# GLEE_Testing_01_Advait.net
KiCad netlist of a schematic drawn in EAGLE
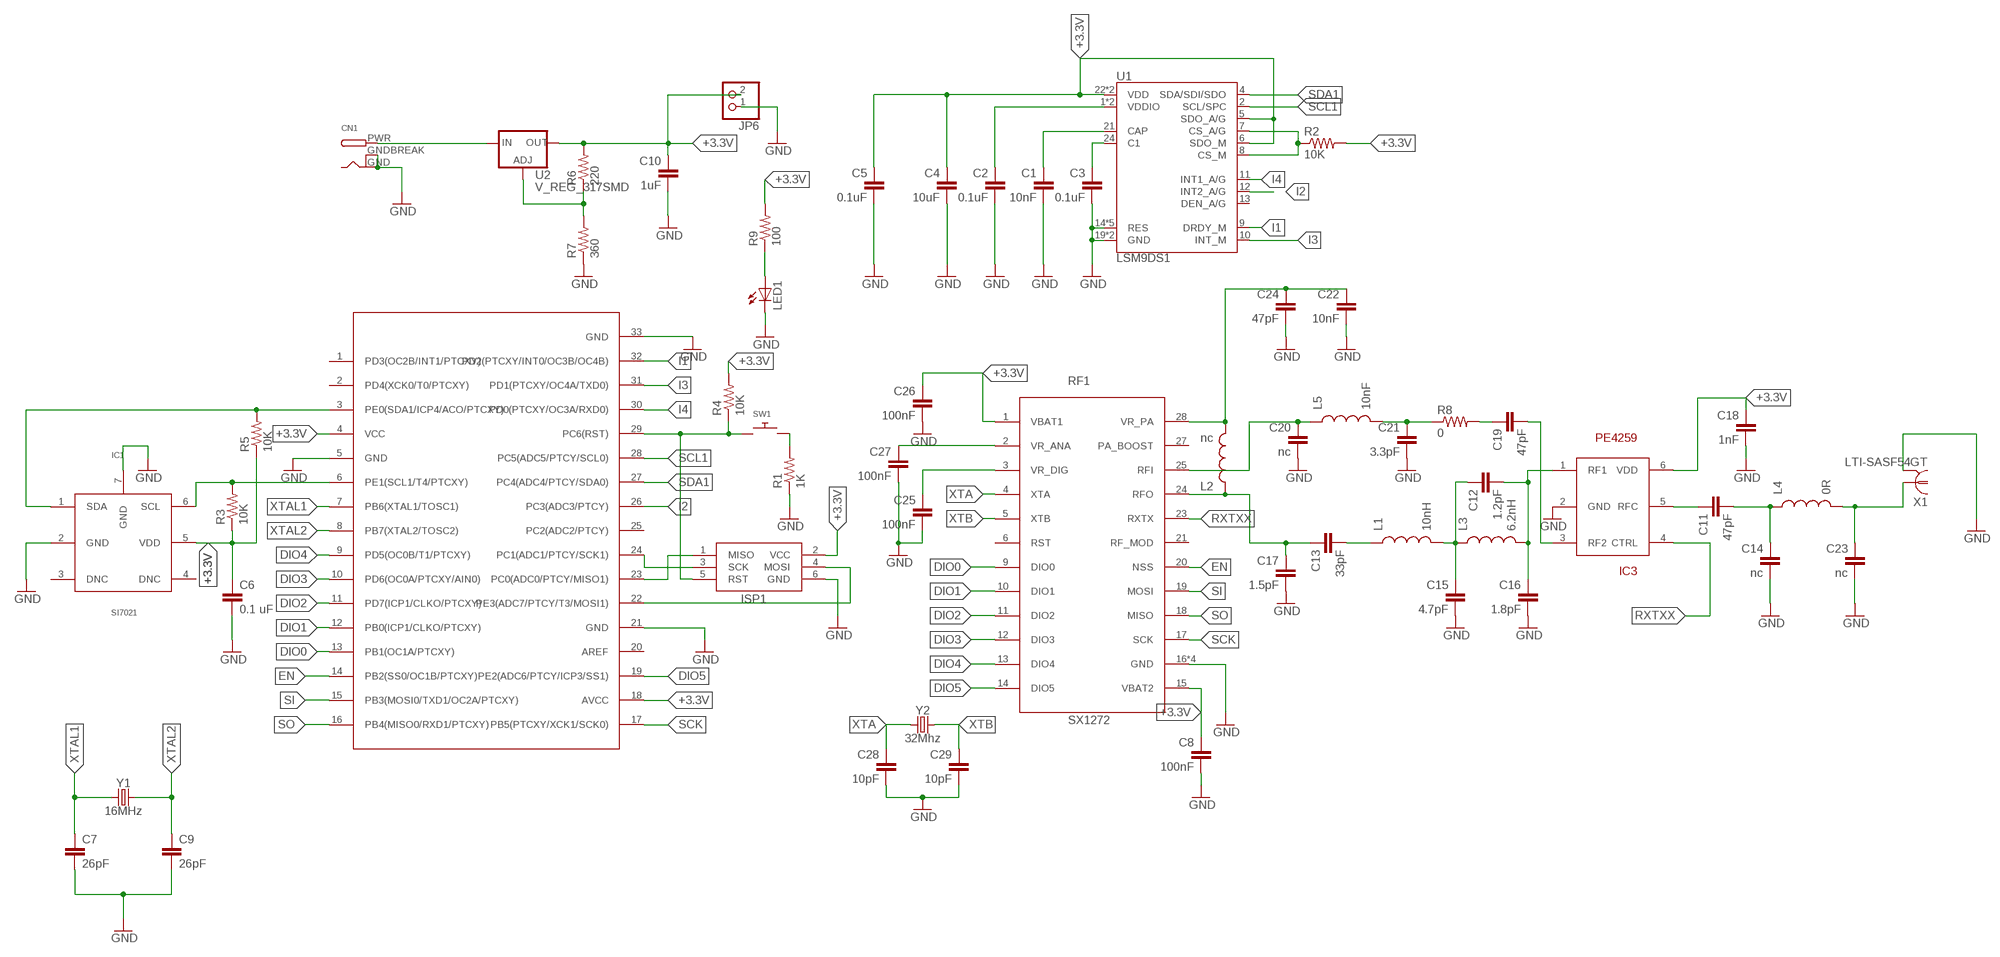
[diagram p0: schematic, sheet 1]

(export (version "E")
  (design (tool "Eeschema 10.0.6"))
  (components
    (comp (ref "C1")
      (value "10nF")
      (footprint "eagle-import:0402-CAP")
      (libsource (lib "eagle-import") (part "CAP0402-CAP"))
    )
    (comp (ref "C2")
      (value "0.1uF")
      (footprint "eagle-import:0402-CAP")
      (libsource (lib "eagle-import") (part "CAP0402-CAP"))
    )
    (comp (ref "C3")
      (value "0.1uF")
      (footprint "eagle-import:0402-CAP")
      (libsource (lib "eagle-import") (part "CAP0402-CAP"))
    )
    (comp (ref "C4")
      (value "10uF")
      (footprint "eagle-import:0402-CAP")
      (libsource (lib "eagle-import") (part "CAP0402-CAP"))
    )
    (comp (ref "C5")
      (value "0.1uF")
      (footprint "eagle-import:0402-CAP")
      (libsource (lib "eagle-import") (part "CAP0402-CAP"))
    )
    (comp (ref "C6")
      (value "0.1 uF")
      (footprint "eagle-import:0402-CAP")
      (libsource (lib "eagle-import") (part "CAP0402-CAP"))
    )
    (comp (ref "C7")
      (value "26pF")
      (footprint "eagle-import:0402-CAP")
      (libsource (lib "eagle-import") (part "CAP0402-CAP"))
    )
    (comp (ref "C8")
      (value "100nF")
      (footprint "eagle-import:0402-CAP")
      (libsource (lib "eagle-import") (part "CAP0402-CAP"))
    )
    (comp (ref "C9")
      (value "26pF")
      (footprint "eagle-import:0402-CAP")
      (libsource (lib "eagle-import") (part "CAP0402-CAP"))
    )
    (comp (ref "C10")
      (value "1uF")
      (footprint "eagle-import:0402-CAP")
      (libsource (lib "eagle-import") (part "CAP0402-CAP"))
    )
    (comp (ref "C11")
      (value "47pF")
      (footprint "eagle-import:0402-CAP")
      (libsource (lib "eagle-import") (part "CAP0402-CAP"))
    )
    (comp (ref "C12")
      (value "1.2pF")
      (footprint "eagle-import:0402-CAP")
      (libsource (lib "eagle-import") (part "CAP0402-CAP"))
    )
    (comp (ref "C13")
      (value "33pF")
      (footprint "eagle-import:0402-CAP")
      (libsource (lib "eagle-import") (part "CAP0402-CAP"))
    )
    (comp (ref "C14")
      (value "nc")
      (footprint "eagle-import:0402-CAP")
      (libsource (lib "eagle-import") (part "CAP0402-CAP"))
    )
    (comp (ref "C15")
      (value "4.7pF")
      (footprint "eagle-import:0402-CAP")
      (libsource (lib "eagle-import") (part "CAP0402-CAP"))
    )
    (comp (ref "C16")
      (value "1.8pF")
      (footprint "eagle-import:0402-CAP")
      (libsource (lib "eagle-import") (part "CAP0402-CAP"))
    )
    (comp (ref "C17")
      (value "1.5pF")
      (footprint "eagle-import:0402-CAP")
      (libsource (lib "eagle-import") (part "CAP0402-CAP"))
    )
    (comp (ref "C18")
      (value "1nF")
      (footprint "eagle-import:0402-CAP")
      (libsource (lib "eagle-import") (part "CAP0402-CAP"))
    )
    (comp (ref "C19")
      (value "47pF")
      (footprint "eagle-import:0402-CAP")
      (libsource (lib "eagle-import") (part "CAP0402-CAP"))
    )
    (comp (ref "C20")
      (value "nc")
      (footprint "eagle-import:0402-CAP")
      (libsource (lib "eagle-import") (part "CAP0402-CAP"))
    )
    (comp (ref "C21")
      (value "3.3pF")
      (footprint "eagle-import:0402-CAP")
      (libsource (lib "eagle-import") (part "CAP0402-CAP"))
    )
    (comp (ref "C22")
      (value "10nF")
      (footprint "eagle-import:0402-CAP")
      (libsource (lib "eagle-import") (part "CAP0402-CAP"))
    )
    (comp (ref "C23")
      (value "nc")
      (footprint "eagle-import:0402-CAP")
      (libsource (lib "eagle-import") (part "CAP0402-CAP"))
    )
    (comp (ref "C24")
      (value "47pF")
      (footprint "eagle-import:0402-CAP")
      (libsource (lib "eagle-import") (part "CAP0402-CAP"))
    )
    (comp (ref "C25")
      (value "100nF")
      (footprint "eagle-import:0402-CAP")
      (libsource (lib "eagle-import") (part "CAP0402-CAP"))
    )
    (comp (ref "C26")
      (value "100nF")
      (footprint "eagle-import:0402-CAP")
      (libsource (lib "eagle-import") (part "CAP0402-CAP"))
    )
    (comp (ref "C27")
      (value "100nF")
      (footprint "eagle-import:0402-CAP")
      (libsource (lib "eagle-import") (part "CAP0402-CAP"))
    )
    (comp (ref "C28")
      (value "10pF")
      (footprint "eagle-import:0402-CAP")
      (libsource (lib "eagle-import") (part "CAP0402-CAP"))
    )
    (comp (ref "C29")
      (value "10pF")
      (footprint "eagle-import:0402-CAP")
      (libsource (lib "eagle-import") (part "CAP0402-CAP"))
    )
    (comp (ref "CN1")
      (value "DCBARRELPTH")
      (footprint "eagle-import:DCJACK_2MM_PTH")
      (libsource (lib "eagle-import") (part "DCBARRELPTH"))
    )
    (comp (ref "IC1")
      (value "SI7021")
      (footprint "eagle-import:SI7021")
      (libsource (lib "eagle-import") (part "SI7021"))
    )
    (comp (ref "IC2")
      (value "ATMEGA328-PB")
      (footprint "eagle-import:ATMEGA328-PB")
      (libsource (lib "eagle-import") (part "ATMEGA328-PB"))
    )
    (comp (ref "IC3")
      (value "PE4259")
      (footprint "eagle-import:PE4259")
      (libsource (lib "eagle-import") (part "PE4259"))
    )
    (comp (ref "ISP1")
      (value "AVRISP-6")
      (footprint "eagle-import:AVRISP")
      (libsource (lib "eagle-import") (part "AVRISP-6"))
    )
    (comp (ref "JP6")
      (value "PINHD-1X2")
      (footprint "eagle-import:1X02")
      (libsource (lib "eagle-import") (part "PINHD-1X2"))
    )
    (comp (ref "L1")
      (value "10nH")
      (footprint "eagle-import:C0402")
      (libsource (lib "eagle-import") (part "INDUCTOR0402"))
    )
    (comp (ref "L2")
      (value "nc")
      (footprint "eagle-import:C0402")
      (libsource (lib "eagle-import") (part "INDUCTOR0402"))
    )
    (comp (ref "L3")
      (value "6.2nH")
      (footprint "eagle-import:C0402")
      (libsource (lib "eagle-import") (part "INDUCTOR0402"))
    )
    (comp (ref "L4")
      (value "0R")
      (footprint "eagle-import:C0402")
      (libsource (lib "eagle-import") (part "INDUCTOR0402"))
    )
    (comp (ref "L5")
      (value "10nF")
      (footprint "eagle-import:C0402")
      (libsource (lib "eagle-import") (part "INDUCTOR0402"))
    )
    (comp (ref "LED1")
      (value "LEDCHIPLED_0805")
      (footprint "eagle-import:CHIPLED_0805")
      (libsource (lib "eagle-import") (part "LEDCHIPLED_0805"))
    )
    (comp (ref "R1")
      (value "1K")
      (footprint "eagle-import:0402-RES")
      (libsource (lib "eagle-import") (part "RESISTOR0402-RES"))
    )
    (comp (ref "R2")
      (value "10K")
      (footprint "eagle-import:0402-RES")
      (libsource (lib "eagle-import") (part "RESISTOR0402-RES"))
    )
    (comp (ref "R3")
      (value "10K")
      (footprint "eagle-import:0402-RES")
      (libsource (lib "eagle-import") (part "RESISTOR0402-RES"))
    )
    (comp (ref "R4")
      (value "10K")
      (footprint "eagle-import:0402-RES")
      (libsource (lib "eagle-import") (part "RESISTOR0402-RES"))
    )
    (comp (ref "R5")
      (value "10K")
      (footprint "eagle-import:0402-RES")
      (libsource (lib "eagle-import") (part "RESISTOR0402-RES"))
    )
    (comp (ref "R6")
      (value "220")
      (footprint "eagle-import:0402-RES")
      (libsource (lib "eagle-import") (part "RESISTOR0402-RES"))
    )
    (comp (ref "R7")
      (value "360")
      (footprint "eagle-import:0402-RES")
      (libsource (lib "eagle-import") (part "RESISTOR0402-RES"))
    )
    (comp (ref "R8")
      (value "0")
      (footprint "eagle-import:0402-RES")
      (libsource (lib "eagle-import") (part "RESISTOR0402-RES"))
    )
    (comp (ref "R9")
      (value "100")
      (footprint "eagle-import:0402-RES")
      (libsource (lib "eagle-import") (part "RESISTOR0402-RES"))
    )
    (comp (ref "RF1")
      (value "SX1272")
      (footprint "eagle-import:SX1272")
      (libsource (lib "eagle-import") (part "SX1272"))
    )
    (comp (ref "SW1")
      (value "SWITCH_PUSHBUTTONSOFTTOUCHSMD_SJ")
      (footprint "eagle-import:PUSHBUTTON_SMD_SJ")
      (libsource (lib "eagle-import") (part "SWITCH_PUSHBUTTONSOFTTOUCHSMD_SJ"))
    )
    (comp (ref "U1")
      (value "LSM9DS1")
      (footprint "eagle-import:LGA24-8X4")
      (libsource (lib "eagle-import") (part "LSM9DS1"))
    )
    (comp (ref "U2")
      (value "V_REG_317SMD")
      (footprint "eagle-import:SOT223")
      (libsource (lib "eagle-import") (part "V_REG_317SMD"))
    )
    (comp (ref "X1")
      (value "LTI-SASF54GT")
      (footprint "eagle-import:LTI-SASF54GT")
      (libsource (lib "eagle-import") (part "LTI-SASF54GT"))
    )
    (comp (ref "Y1")
      (value "16MHz")
      (footprint "eagle-import:CRYSTAL-SMD-2.0X1.6MM")
      (libsource (lib "eagle-import") (part "CRYSTAL-16MHZSMD-2X1.6"))
    )
    (comp (ref "Y2")
      (value "32Mhz")
      (footprint "eagle-import:CRYSTAL-SMD-2.0X1.6MM")
      (libsource (lib "eagle-import") (part "CRYSTAL-16MHZSMD-2X1.6"))
    )
  )
  (nets
    (net (code "1") (name "+3.3V") (class "Default")
      (node (ref "C10") (pin "1") (pinfunction "1_1") (pintype "passive"))
      (node (ref "C18") (pin "1") (pinfunction "1_1") (pintype "passive"))
      (node (ref "C26") (pin "1") (pinfunction "1_1") (pintype "passive"))
      (node (ref "C4") (pin "1") (pinfunction "1_1") (pintype "passive"))
      (node (ref "C5") (pin "1") (pinfunction "1_1") (pintype "passive"))
      (node (ref "C6") (pin "1") (pinfunction "1_1") (pintype "passive"))
      (node (ref "C8") (pin "1") (pinfunction "1_1") (pintype "passive"))
      (node (ref "IC1") (pin "5") (pinfunction "VDD_5") (pintype "bidirectional"))
      (node (ref "IC2") (pin "18") (pinfunction "AVCC_18") (pintype "bidirectional"))
      (node (ref "IC2") (pin "4") (pinfunction "VCC_4") (pintype "bidirectional"))
      (node (ref "IC3") (pin "6") (pinfunction "VDD_6") (pintype "bidirectional"))
      (node (ref "ISP1") (pin "2") (pinfunction "VCC_2") (pintype "power_in"))
      (node (ref "JP6") (pin "2") (pinfunction "2_2") (pintype "passive"))
      (node (ref "R2") (pin "2") (pinfunction "2_2") (pintype "passive"))
      (node (ref "R3") (pin "1") (pinfunction "1_1") (pintype "passive"))
      (node (ref "R4") (pin "2") (pinfunction "2_2") (pintype "passive"))
      (node (ref "R5") (pin "1") (pinfunction "1_1") (pintype "passive"))
      (node (ref "R6") (pin "2") (pinfunction "2_2") (pintype "passive"))
      (node (ref "R9") (pin "2") (pinfunction "2_2") (pintype "passive"))
      (node (ref "RF1") (pin "1") (pinfunction "VBAT1_1") (pintype "bidirectional"))
      (node (ref "RF1") (pin "15") (pinfunction "VBAT2_15") (pintype "bidirectional"))
      (node (ref "U1") (pin "22") (pinfunction "VDD_22") (pintype "bidirectional"))
      (node (ref "U1") (pin "23") (pinfunction "VDD_23") (pintype "bidirectional"))
      (node (ref "U1") (pin "5") (pinfunction "SDO_A/G_5") (pintype "bidirectional"))
      (node (ref "U1") (pin "6") (pinfunction "SDO_M_6") (pintype "bidirectional"))
      (node (ref "U2") (pin "2") (pinfunction "OUT_2") (pintype "output"))
    )
    (net (code "2") (name "DIO0") (class "Default")
      (node (ref "IC2") (pin "13") (pinfunction "PB1(OC1A/PTCXY)_13") (pintype "bidirectional"))
      (node (ref "RF1") (pin "9") (pinfunction "DIO0_9") (pintype "bidirectional"))
    )
    (net (code "3") (name "DIO1") (class "Default")
      (node (ref "IC2") (pin "12") (pinfunction "PB0(ICP1/CLKO/PTCXY)_12") (pintype "bidirectional"))
      (node (ref "RF1") (pin "10") (pinfunction "DIO1_10") (pintype "bidirectional"))
    )
    (net (code "4") (name "DIO2") (class "Default")
      (node (ref "IC2") (pin "11") (pinfunction "PD7(ICP1/CLKO/PTCXY)_11") (pintype "bidirectional"))
      (node (ref "RF1") (pin "11") (pinfunction "DIO2_11") (pintype "bidirectional"))
    )
    (net (code "5") (name "DIO3") (class "Default")
      (node (ref "IC2") (pin "10") (pinfunction "PD6(OC0A/PTCXY/AIN0)_10") (pintype "bidirectional"))
      (node (ref "RF1") (pin "12") (pinfunction "DIO3_12") (pintype "bidirectional"))
    )
    (net (code "6") (name "DIO4") (class "Default")
      (node (ref "IC2") (pin "9") (pinfunction "PD5(OC0B/T1/PTCXY)_9") (pintype "bidirectional"))
      (node (ref "RF1") (pin "13") (pinfunction "DIO4_13") (pintype "bidirectional"))
    )
    (net (code "7") (name "DIO5") (class "Default")
      (node (ref "IC2") (pin "19") (pinfunction "PE2(ADC6/PTCY/ICP3/SS1)_19") (pintype "bidirectional"))
      (node (ref "RF1") (pin "14") (pinfunction "DIO5_14") (pintype "bidirectional"))
    )
    (net (code "8") (name "EN") (class "Default")
      (node (ref "IC2") (pin "14") (pinfunction "PB2(SS0/OC1B/PTCXY)_14") (pintype "bidirectional"))
      (node (ref "RF1") (pin "20") (pinfunction "NSS_20") (pintype "bidirectional"))
    )
    (net (code "9") (name "GND") (class "Default")
      (node (ref "C1") (pin "2") (pinfunction "2_2") (pintype "passive"))
      (node (ref "C10") (pin "2") (pinfunction "2_2") (pintype "passive"))
      (node (ref "C14") (pin "2") (pinfunction "2_2") (pintype "passive"))
      (node (ref "C15") (pin "2") (pinfunction "2_2") (pintype "passive"))
      (node (ref "C16") (pin "2") (pinfunction "2_2") (pintype "passive"))
      (node (ref "C17") (pin "2") (pinfunction "2_2") (pintype "passive"))
      (node (ref "C18") (pin "2") (pinfunction "2_2") (pintype "passive"))
      (node (ref "C2") (pin "2") (pinfunction "2_2") (pintype "passive"))
      (node (ref "C20") (pin "2") (pinfunction "2_2") (pintype "passive"))
      (node (ref "C21") (pin "2") (pinfunction "2_2") (pintype "passive"))
      (node (ref "C22") (pin "2") (pinfunction "2_2") (pintype "passive"))
      (node (ref "C23") (pin "2") (pinfunction "2_2") (pintype "passive"))
      (node (ref "C24") (pin "2") (pinfunction "2_2") (pintype "passive"))
      (node (ref "C25") (pin "2") (pinfunction "2_2") (pintype "passive"))
      (node (ref "C26") (pin "2") (pinfunction "2_2") (pintype "passive"))
      (node (ref "C27") (pin "2") (pinfunction "2_2") (pintype "passive"))
      (node (ref "C28") (pin "2") (pinfunction "2_2") (pintype "passive"))
      (node (ref "C29") (pin "2") (pinfunction "2_2") (pintype "passive"))
      (node (ref "C3") (pin "2") (pinfunction "2_2") (pintype "passive"))
      (node (ref "C4") (pin "2") (pinfunction "2_2") (pintype "passive"))
      (node (ref "C5") (pin "2") (pinfunction "2_2") (pintype "passive"))
      (node (ref "C6") (pin "2") (pinfunction "2_2") (pintype "passive"))
      (node (ref "C7") (pin "2") (pinfunction "2_2") (pintype "passive"))
      (node (ref "C8") (pin "2") (pinfunction "2_2") (pintype "passive"))
      (node (ref "C9") (pin "2") (pinfunction "2_2") (pintype "passive"))
      (node (ref "CN1") (pin "GND") (pinfunction "GND_GND") (pintype "power_in"))
      (node (ref "CN1") (pin "GNDBREAK") (pinfunction "GNDBREAK_GNDBREAK") (pintype "power_in"))
      (node (ref "IC1") (pin "2") (pinfunction "GND_2") (pintype "bidirectional"))
      (node (ref "IC1") (pin "7") (pinfunction "GND_7") (pintype "bidirectional"))
      (node (ref "IC2") (pin "21") (pinfunction "GND_21") (pintype "bidirectional"))
      (node (ref "IC2") (pin "33") (pinfunction "GND_33") (pintype "bidirectional"))
      (node (ref "IC2") (pin "5") (pinfunction "GND_5") (pintype "bidirectional"))
      (node (ref "IC3") (pin "2") (pinfunction "GND_2") (pintype "bidirectional"))
      (node (ref "ISP1") (pin "6") (pinfunction "GND_6") (pintype "power_in"))
      (node (ref "JP6") (pin "1") (pinfunction "1_1") (pintype "passive"))
      (node (ref "LED1") (pin "C") (pinfunction "C_C") (pintype "passive"))
      (node (ref "R1") (pin "1") (pinfunction "1_1") (pintype "passive"))
      (node (ref "R7") (pin "1") (pinfunction "1_1") (pintype "passive"))
      (node (ref "RF1") (pin "16") (pinfunction "GND_16") (pintype "bidirectional"))
      (node (ref "RF1") (pin "22") (pinfunction "GND_22") (pintype "bidirectional"))
      (node (ref "RF1") (pin "26") (pinfunction "GND_26") (pintype "bidirectional"))
      (node (ref "RF1") (pin "29") (pinfunction "GND_29") (pintype "bidirectional"))
      (node (ref "U1") (pin "14") (pinfunction "RES_14") (pintype "bidirectional"))
      (node (ref "U1") (pin "15") (pinfunction "RES_15") (pintype "bidirectional"))
      (node (ref "U1") (pin "16") (pinfunction "RES_16") (pintype "bidirectional"))
      (node (ref "U1") (pin "17") (pinfunction "RES_17") (pintype "bidirectional"))
      (node (ref "U1") (pin "18") (pinfunction "RES_18") (pintype "bidirectional"))
      (node (ref "U1") (pin "19") (pinfunction "GND_19") (pintype "bidirectional"))
      (node (ref "U1") (pin "20") (pinfunction "GND_20") (pintype "bidirectional"))
      (node (ref "X1") (pin "2") (pinfunction "2_2") (pintype "passive"))
      (node (ref "X1") (pin "3") (pinfunction "2_3") (pintype "passive"))
      (node (ref "X1") (pin "4") (pinfunction "2_4") (pintype "passive"))
      (node (ref "X1") (pin "5") (pinfunction "2_5") (pintype "passive"))
    )
    (net (code "10") (name "I1") (class "Default")
      (node (ref "IC2") (pin "32") (pinfunction "PD2(PTCXY/INT0/OC3B/OC4B)_32") (pintype "bidirectional"))
      (node (ref "U1") (pin "9") (pinfunction "DRDY_M_9") (pintype "bidirectional"))
    )
    (net (code "11") (name "I2") (class "Default")
      (node (ref "IC2") (pin "26") (pinfunction "PC3(ADC3/PTCY)_26") (pintype "bidirectional"))
      (node (ref "U1") (pin "12") (pinfunction "INT2_A/G_12") (pintype "bidirectional"))
    )
    (net (code "12") (name "I3") (class "Default")
      (node (ref "IC2") (pin "31") (pinfunction "PD1(PTCXY/OC4A/TXD0)_31") (pintype "bidirectional"))
      (node (ref "U1") (pin "10") (pinfunction "INT_M_10") (pintype "bidirectional"))
    )
    (net (code "13") (name "I4") (class "Default")
      (node (ref "IC2") (pin "30") (pinfunction "PD0(PTCXY/OC3A/RXD0)_30") (pintype "bidirectional"))
      (node (ref "U1") (pin "11") (pinfunction "INT1_A/G_11") (pintype "bidirectional"))
    )
    (net (code "14") (name "Net-(C2-Pad1)") (class "Default")
      (node (ref "C2") (pin "1") (pinfunction "1_1") (pintype "passive"))
      (node (ref "U1") (pin "1") (pinfunction "VDDIO_1") (pintype "bidirectional"))
      (node (ref "U1") (pin "3") (pinfunction "VDDIO_3") (pintype "bidirectional"))
    )
    (net (code "15") (name "Net-(C11-Pad2)") (class "Default")
      (node (ref "C11") (pin "2") (pinfunction "2_2") (pintype "passive"))
      (node (ref "C14") (pin "1") (pinfunction "1_1") (pintype "passive"))
      (node (ref "L4") (pin "1") (pinfunction "1_1") (pintype "passive"))
    )
    (net (code "16") (name "Net-(C12-Pad1)") (class "Default")
      (node (ref "C12") (pin "1") (pinfunction "1_1") (pintype "passive"))
      (node (ref "C15") (pin "1") (pinfunction "1_1") (pintype "passive"))
      (node (ref "L1") (pin "2") (pinfunction "2_2") (pintype "passive"))
      (node (ref "L3") (pin "1") (pinfunction "1_1") (pintype "passive"))
    )
    (net (code "17") (name "Net-(C13-Pad2)") (class "Default")
      (node (ref "C13") (pin "2") (pinfunction "2_2") (pintype "passive"))
      (node (ref "L1") (pin "1") (pinfunction "1_1") (pintype "passive"))
    )
    (net (code "18") (name "Net-(C19-Pad1)") (class "Default")
      (node (ref "C19") (pin "1") (pinfunction "1_1") (pintype "passive"))
      (node (ref "R8") (pin "2") (pinfunction "2_2") (pintype "passive"))
    )
    (net (code "19") (name "Net-(C21-Pad1)") (class "Default")
      (node (ref "C21") (pin "1") (pinfunction "1_1") (pintype "passive"))
      (node (ref "L5") (pin "2") (pinfunction "2_2") (pintype "passive"))
      (node (ref "R8") (pin "1") (pinfunction "1_1") (pintype "passive"))
    )
    (net (code "20") (name "Net-(C23-Pad1)") (class "Default")
      (node (ref "C23") (pin "1") (pinfunction "1_1") (pintype "passive"))
      (node (ref "L4") (pin "2") (pinfunction "2_2") (pintype "passive"))
      (node (ref "X1") (pin "1") (pinfunction "1_1") (pintype "passive"))
    )
    (net (code "21") (name "Net-(IC1-SCL)") (class "Default")
      (node (ref "IC1") (pin "6") (pinfunction "SCL_6") (pintype "bidirectional"))
      (node (ref "IC2") (pin "6") (pinfunction "PE1(SCL1/T4/PTCXY)_6") (pintype "bidirectional"))
      (node (ref "R3") (pin "2") (pinfunction "2_2") (pintype "passive"))
    )
    (net (code "22") (name "Net-(IC1-SDA)") (class "Default")
      (node (ref "IC1") (pin "1") (pinfunction "SDA_1") (pintype "bidirectional"))
      (node (ref "IC2") (pin "3") (pinfunction "PE0(SDA1/ICP4/ACO/PTCXY)_3") (pintype "bidirectional"))
      (node (ref "R5") (pin "2") (pinfunction "2_2") (pintype "passive"))
    )
    (net (code "23") (name "Net-(IC2-PC0(ADC0{slash}PTCY{slash}MISO1))") (class "Default")
      (node (ref "IC2") (pin "23") (pinfunction "PC0(ADC0/PTCY/MISO1)_23") (pintype "bidirectional"))
      (node (ref "ISP1") (pin "1") (pinfunction "MISO_1") (pintype "input"))
    )
    (net (code "24") (name "Net-(IC2-PC1(ADC1{slash}PTCY{slash}SCK1))") (class "Default")
      (node (ref "IC2") (pin "24") (pinfunction "PC1(ADC1/PTCY/SCK1)_24") (pintype "bidirectional"))
      (node (ref "ISP1") (pin "3") (pinfunction "SCK_3") (pintype "output"))
    )
    (net (code "25") (name "Net-(IC2-PC6(RST))") (class "Default")
      (node (ref "IC2") (pin "29") (pinfunction "PC6(RST)_29") (pintype "bidirectional"))
      (node (ref "ISP1") (pin "5") (pinfunction "RST_5") (pintype "output"))
      (node (ref "R4") (pin "1") (pinfunction "1_1") (pintype "passive"))
      (node (ref "SW1") (pin "P$1") (pinfunction "P$1_P$1") (pintype "passive"))
    )
    (net (code "26") (name "Net-(IC2-PE3(ADC7{slash}PTCY{slash}T3{slash}MOSI1))") (class "Default")
      (node (ref "IC2") (pin "22") (pinfunction "PE3(ADC7/PTCY/T3/MOSI1)_22") (pintype "bidirectional"))
      (node (ref "ISP1") (pin "4") (pinfunction "MOSI_4") (pintype "output"))
    )
    (net (code "27") (name "Net-(IC3-RF1)") (class "Default")
      (node (ref "C12") (pin "2") (pinfunction "2_2") (pintype "passive"))
      (node (ref "C16") (pin "1") (pinfunction "1_1") (pintype "passive"))
      (node (ref "IC3") (pin "1") (pinfunction "RF1_1") (pintype "bidirectional"))
      (node (ref "L3") (pin "2") (pinfunction "2_2") (pintype "passive"))
    )
    (net (code "28") (name "Net-(IC3-RF2)") (class "Default")
      (node (ref "C19") (pin "2") (pinfunction "2_2") (pintype "passive"))
      (node (ref "IC3") (pin "3") (pinfunction "RF2_3") (pintype "bidirectional"))
    )
    (net (code "29") (name "Net-(IC3-RFC)") (class "Default")
      (node (ref "C11") (pin "1") (pinfunction "1_1") (pintype "passive"))
      (node (ref "IC3") (pin "5") (pinfunction "RFC_5") (pintype "bidirectional"))
    )
    (net (code "30") (name "Net-(LED1-PadA)") (class "Default")
      (node (ref "LED1") (pin "A") (pinfunction "A_A") (pintype "passive"))
      (node (ref "R9") (pin "1") (pinfunction "1_1") (pintype "passive"))
    )
    (net (code "31") (name "Net-(R1-Pad2)") (class "Default")
      (node (ref "R1") (pin "2") (pinfunction "2_2") (pintype "passive"))
      (node (ref "SW1") (pin "P$2") (pinfunction "P$2_P$2") (pintype "passive"))
    )
    (net (code "32") (name "Net-(RF1-RFI)") (class "Default")
      (node (ref "C20") (pin "1") (pinfunction "1_1") (pintype "passive"))
      (node (ref "L5") (pin "1") (pinfunction "1_1") (pintype "passive"))
      (node (ref "RF1") (pin "25") (pinfunction "RFI_25") (pintype "bidirectional"))
    )
    (net (code "33") (name "Net-(RF1-RFO)") (class "Default")
      (node (ref "C13") (pin "1") (pinfunction "1_1") (pintype "passive"))
      (node (ref "C17") (pin "1") (pinfunction "1_1") (pintype "passive"))
      (node (ref "L2") (pin "1") (pinfunction "1_1") (pintype "passive"))
      (node (ref "RF1") (pin "24") (pinfunction "RFO_24") (pintype "bidirectional"))
    )
    (net (code "34") (name "Net-(RF1-VR_ANA)") (class "Default")
      (node (ref "C27") (pin "1") (pinfunction "1_1") (pintype "passive"))
      (node (ref "RF1") (pin "2") (pinfunction "VR_ANA_2") (pintype "bidirectional"))
    )
    (net (code "35") (name "Net-(RF1-VR_DIG)") (class "Default")
      (node (ref "C25") (pin "1") (pinfunction "1_1") (pintype "passive"))
      (node (ref "RF1") (pin "3") (pinfunction "VR_DIG_3") (pintype "bidirectional"))
    )
    (net (code "36") (name "Net-(RF1-VR_PA)") (class "Default")
      (node (ref "C22") (pin "1") (pinfunction "1_1") (pintype "passive"))
      (node (ref "C24") (pin "1") (pinfunction "1_1") (pintype "passive"))
      (node (ref "L2") (pin "2") (pinfunction "2_2") (pintype "passive"))
      (node (ref "RF1") (pin "28") (pinfunction "VR_PA_28") (pintype "bidirectional"))
    )
    (net (code "37") (name "Net-(U1-C1)") (class "Default")
      (node (ref "C3") (pin "1") (pinfunction "1_1") (pintype "passive"))
      (node (ref "U1") (pin "24") (pinfunction "C1_24") (pintype "bidirectional"))
    )
    (net (code "38") (name "Net-(U1-CAP)") (class "Default")
      (node (ref "C1") (pin "1") (pinfunction "1_1") (pintype "passive"))
      (node (ref "U1") (pin "21") (pinfunction "CAP_21") (pintype "bidirectional"))
    )
    (net (code "39") (name "Net-(U1-CS_A{slash}G)") (class "Default")
      (node (ref "R2") (pin "1") (pinfunction "1_1") (pintype "passive"))
      (node (ref "U1") (pin "7") (pinfunction "CS_A/G_7") (pintype "bidirectional"))
      (node (ref "U1") (pin "8") (pinfunction "CS_M_8") (pintype "bidirectional"))
    )
    (net (code "40") (name "Net-(U2-ADJ)") (class "Default")
      (node (ref "R6") (pin "1") (pinfunction "1_1") (pintype "passive"))
      (node (ref "R7") (pin "2") (pinfunction "2_2") (pintype "passive"))
      (node (ref "U2") (pin "1") (pinfunction "ADJ_1") (pintype "input"))
    )
    (net (code "41") (name "Net-(U2-IN)") (class "Default")
      (node (ref "CN1") (pin "PWR") (pinfunction "PWR_PWR") (pintype "power_in"))
      (node (ref "U2") (pin "3") (pinfunction "IN_3") (pintype "input"))
    )
    (net (code "42") (name "RXTXX") (class "Default")
      (node (ref "IC3") (pin "4") (pinfunction "CTRL_4") (pintype "bidirectional"))
      (node (ref "RF1") (pin "23") (pinfunction "RXTX_23") (pintype "bidirectional"))
    )
    (net (code "43") (name "SCK") (class "Default")
      (node (ref "IC2") (pin "17") (pinfunction "PB5(PTCXY/XCK1/SCK0)_17") (pintype "bidirectional"))
      (node (ref "RF1") (pin "17") (pinfunction "SCK_17") (pintype "bidirectional"))
    )
    (net (code "44") (name "SCL1") (class "Default")
      (node (ref "IC2") (pin "28") (pinfunction "PC5(ADC5/PTCY/SCL0)_28") (pintype "bidirectional"))
      (node (ref "U1") (pin "2") (pinfunction "SCL/SPC_2") (pintype "bidirectional"))
    )
    (net (code "45") (name "SDA1") (class "Default")
      (node (ref "IC2") (pin "27") (pinfunction "PC4(ADC4/PTCY/SDA0)_27") (pintype "bidirectional"))
      (node (ref "U1") (pin "4") (pinfunction "SDA/SDI/SDO_4") (pintype "bidirectional"))
    )
    (net (code "46") (name "SI") (class "Default")
      (node (ref "IC2") (pin "15") (pinfunction "PB3(MOSI0/TXD1/OC2A/PTCXY)_15") (pintype "bidirectional"))
      (node (ref "RF1") (pin "19") (pinfunction "MOSI_19") (pintype "bidirectional"))
    )
    (net (code "47") (name "SO") (class "Default")
      (node (ref "IC2") (pin "16") (pinfunction "PB4(MISO0/RXD1/PTCXY)_16") (pintype "bidirectional"))
      (node (ref "RF1") (pin "18") (pinfunction "MISO_18") (pintype "bidirectional"))
    )
    (net (code "48") (name "XTA") (class "Default")
      (node (ref "C28") (pin "1") (pinfunction "1_1") (pintype "passive"))
      (node (ref "RF1") (pin "4") (pinfunction "XTA_4") (pintype "bidirectional"))
      (node (ref "Y2") (pin "1") (pinfunction "1_1") (pintype "passive"))
    )
    (net (code "49") (name "XTAL1") (class "Default")
      (node (ref "C7") (pin "1") (pinfunction "1_1") (pintype "passive"))
      (node (ref "IC2") (pin "7") (pinfunction "PB6(XTAL1/TOSC1)_7") (pintype "bidirectional"))
      (node (ref "Y1") (pin "1") (pinfunction "1_1") (pintype "passive"))
    )
    (net (code "50") (name "XTAL2") (class "Default")
      (node (ref "C9") (pin "1") (pinfunction "1_1") (pintype "passive"))
      (node (ref "IC2") (pin "8") (pinfunction "PB7(XTAL2/TOSC2)_8") (pintype "bidirectional"))
      (node (ref "Y1") (pin "3") (pinfunction "2_3") (pintype "passive"))
    )
    (net (code "51") (name "XTB") (class "Default")
      (node (ref "C29") (pin "1") (pinfunction "1_1") (pintype "passive"))
      (node (ref "RF1") (pin "5") (pinfunction "XTB_5") (pintype "bidirectional"))
      (node (ref "Y2") (pin "3") (pinfunction "2_3") (pintype "passive"))
    )
    (net (code "52") (name "unconnected-(IC1-DNC-Pad3)") (class "Default")
      (node (ref "IC1") (pin "3") (pinfunction "DNC_3") (pintype "bidirectional"))
    )
    (net (code "53") (name "unconnected-(IC1-DNC-Pad4)") (class "Default")
      (node (ref "IC1") (pin "4") (pinfunction "DNC_4") (pintype "bidirectional"))
    )
    (net (code "54") (name "unconnected-(IC2-AREF-Pad20)") (class "Default")
      (node (ref "IC2") (pin "20") (pinfunction "AREF_20") (pintype "bidirectional"))
    )
    (net (code "55") (name "unconnected-(IC2-PC2(ADC2{slash}PTCY)-Pad25)") (class "Default")
      (node (ref "IC2") (pin "25") (pinfunction "PC2(ADC2/PTCY)_25") (pintype "bidirectional"))
    )
    (net (code "56") (name "unconnected-(IC2-PD3(OC2B{slash}INT1{slash}PTCXY)-Pad1)") (class "Default")
      (node (ref "IC2") (pin "1") (pinfunction "PD3(OC2B/INT1/PTCXY)_1") (pintype "bidirectional"))
    )
    (net (code "57") (name "unconnected-(IC2-PD4(XCK0{slash}T0{slash}PTCXY)-Pad2)") (class "Default")
      (node (ref "IC2") (pin "2") (pinfunction "PD4(XCK0/T0/PTCXY)_2") (pintype "bidirectional"))
    )
    (net (code "58") (name "unconnected-(RF1-PA_BOOST-Pad27)") (class "Default")
      (node (ref "RF1") (pin "27") (pinfunction "PA_BOOST_27") (pintype "bidirectional"))
    )
    (net (code "59") (name "unconnected-(RF1-RF_MOD-Pad21)") (class "Default")
      (node (ref "RF1") (pin "21") (pinfunction "RF_MOD_21") (pintype "bidirectional"))
    )
    (net (code "60") (name "unconnected-(RF1-RST-Pad6)") (class "Default")
      (node (ref "RF1") (pin "6") (pinfunction "RST_6") (pintype "bidirectional"))
    )
    (net (code "61") (name "unconnected-(U1-DEN_A{slash}G-Pad13)") (class "Default")
      (node (ref "U1") (pin "13") (pinfunction "DEN_A/G_13") (pintype "bidirectional"))
    )
  )
)
